# PCBBoardlayout.net
KiCad netlist of a schematic drawn in Altium Designer
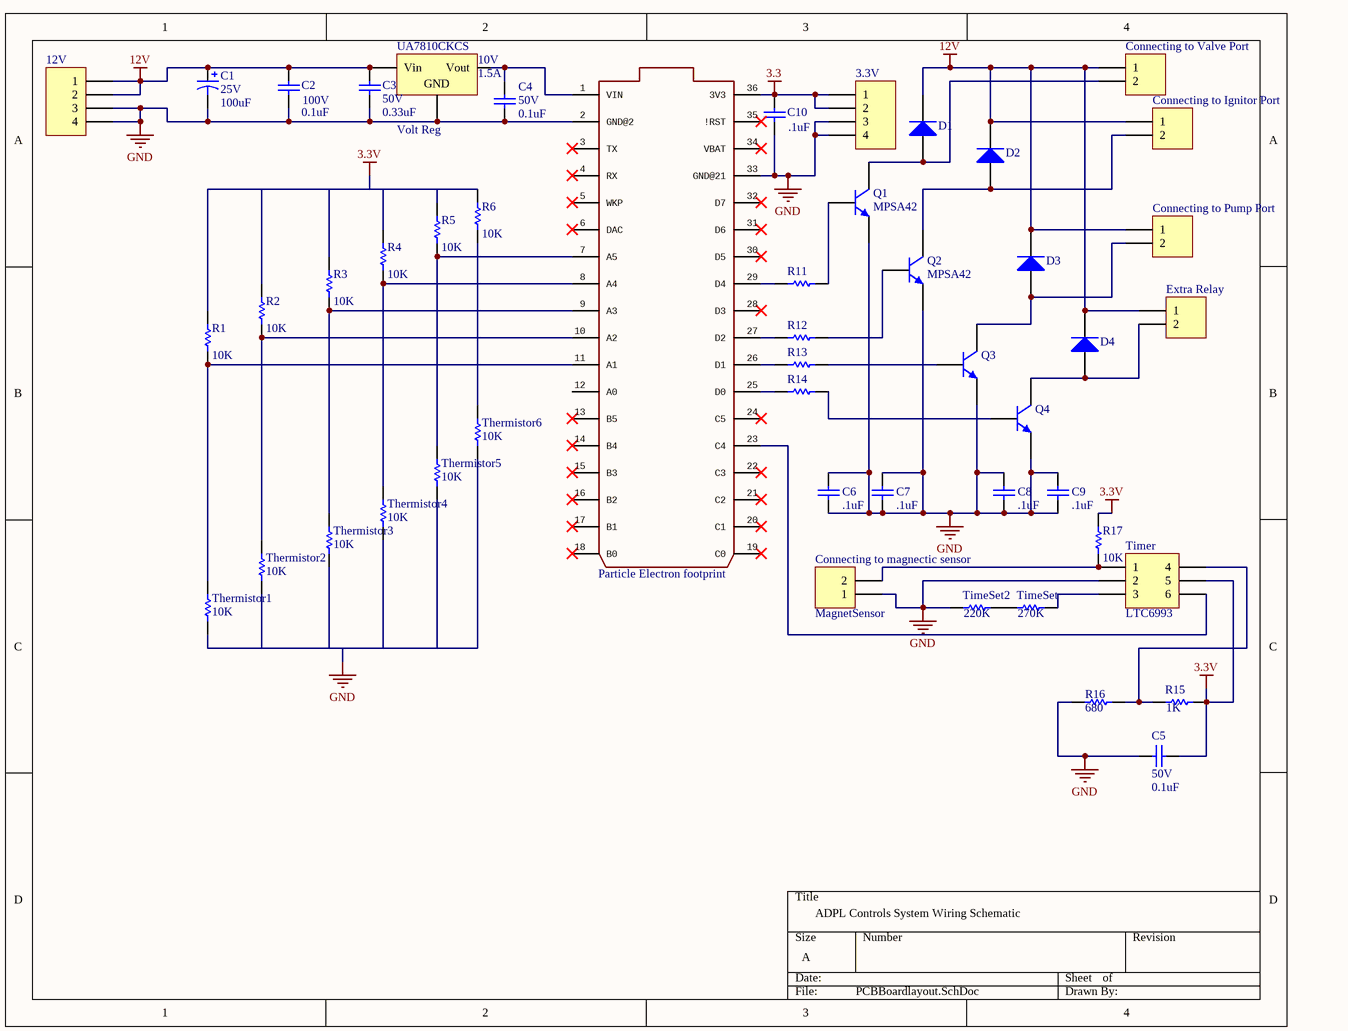
[diagram p0: PCBBoardlayout.SchDoc]

(export (version "E")
  (design (tool "Eeschema 10.0.6"))
  (components
    (comp (ref "3.3V")
      (value "~")
      (footprint "HDR1X4")
      (description "Header, 4-Pin")
      (fields (field (name "PUBLISHER") "Altium Limited"))
      (libsource (lib "Miscellaneous Connectors") (part "Header 4"))
    )
    (comp (ref "12V")
      (value "~")
      (footprint "HDR1X2")
      (description "Header, 4-Pin")
      (fields (field (name "PUBLISHER") "Altium Limited"))
      (libsource (lib "") (part "Header 4_1"))
    )
    (comp (ref "C1")
      (value "25V")
      (footprint "RB7.6-15")
      (description "Polarized Capacitor (Radial)")
      (fields (field (name "ALTIUM_VALUE") "100uF") (field (name "PUBLISHER") "Altium Limited"))
      (libsource (lib "Miscellaneous Devices") (part "Cap Pol1"))
    )
    (comp (ref "C2")
      (value "100V")
      (footprint "C1206")
      (description "Capacitor (Semiconductor SIM Model)")
      (fields
        (field (name "ALTIUM_VALUE") "0.1uF")
        (field (name "PART#") "581-SA111E104MAR")
        (field (name "PUBLISHER") "Altium Limited")
      )
      (libsource (lib "Miscellaneous Devices") (part "Cap Semi"))
    )
    (comp (ref "C3")
      (value "50V")
      (footprint "RAD-0.3")
      (description "Capacitor")
      (fields (field (name "ALTIUM_VALUE") "0.33uF") (field (name "PUBLISHER") "Altium Limited"))
      (libsource (lib "Miscellaneous Devices") (part "Cap"))
    )
    (comp (ref "C4")
      (value "50V")
      (footprint "RAD-0.3")
      (description "Capacitor")
      (fields (field (name "ALTIUM_VALUE") "0.1uF") (field (name "PUBLISHER") "Altium Limited"))
      (libsource (lib "Miscellaneous Devices") (part "Cap"))
    )
    (comp (ref "C5")
      (value "50V")
      (footprint "RAD-0.3")
      (description "Capacitor")
      (fields (field (name "ALTIUM_VALUE") "0.1uF") (field (name "PUBLISHER") "Altium Limited"))
      (libsource (lib "Miscellaneous Devices") (part "Cap"))
    )
    (comp (ref "C6")
      (value ".1uF")
      (footprint "C1206")
      (description "Capacitor (Semiconductor SIM Model)")
      (fields
        (field (name "PART#") "581-SA111E104MAR")
        (field (name "Comment") "BYCap")
        (field (name "PUBLISHER") "Altium Limited")
      )
      (libsource (lib "Miscellaneous Devices") (part "Cap Semi"))
    )
    (comp (ref "C7")
      (value ".1uF")
      (footprint "C1206")
      (description "Capacitor (Semiconductor SIM Model)")
      (fields
        (field (name "PART#") "581-SA111E104MAR")
        (field (name "Comment") "BYCap")
        (field (name "PUBLISHER") "Altium Limited")
      )
      (libsource (lib "Miscellaneous Devices") (part "Cap Semi"))
    )
    (comp (ref "C8")
      (value ".1uF")
      (footprint "C1206")
      (description "Capacitor (Semiconductor SIM Model)")
      (fields
        (field (name "PART#") "581-SA111E104MAR")
        (field (name "Comment") "BYCap")
        (field (name "PUBLISHER") "Altium Limited")
      )
      (libsource (lib "Miscellaneous Devices") (part "Cap Semi"))
    )
    (comp (ref "C9")
      (value ".1uF")
      (footprint "C1206")
      (description "Capacitor (Semiconductor SIM Model)")
      (fields
        (field (name "PART#") "581-SA111E104MAR")
        (field (name "Comment") "BYCap")
        (field (name "PUBLISHER") "Altium Limited")
      )
      (libsource (lib "Miscellaneous Devices") (part "Cap Semi"))
    )
    (comp (ref "C10")
      (value ".1uF")
      (footprint "C1206")
      (description "Capacitor (Semiconductor SIM Model)")
      (fields
        (field (name "PART#") "581-SA111E104MAR")
        (field (name "Comment") "BYCap")
        (field (name "PUBLISHER") "Altium Limited")
      )
      (libsource (lib "Miscellaneous Devices") (part "Cap Semi"))
    )
    (comp (ref "Connecting to Ignitor Port")
      (value "~")
      (footprint "HDR1X2")
      (description "Header, 2-Pin")
      (fields (field (name "PUBLISHER") "Altium Limited"))
      (libsource (lib "Miscellaneous Connectors") (part "Header 2"))
    )
    (comp (ref "Connecting to magnectic sensor")
      (value "MagnetSensor")
      (footprint "HDR1X2")
      (description "Header, 2-Pin")
      (fields
        (field (name "PUBLISHER") "Altium Limited")
        (field (name "SOURCE") "http://www.amazon.com/GERI-Counter-Digital-Proximity-Magnetic/dp/B01875612U/ref=sr_1_2?ie=UTF8&qid=1456764906&sr=8-2&keywords=magnetic+counter")
      )
      (libsource (lib "") (part "Header 2_1"))
    )
    (comp (ref "Connecting to Pump Port")
      (value "~")
      (footprint "HDR1X2")
      (description "Header, 2-Pin")
      (fields (field (name "PUBLISHER") "Altium Limited"))
      (libsource (lib "Miscellaneous Connectors") (part "Header 2"))
    )
    (comp (ref "Connecting to Valve Port")
      (value "~")
      (footprint "HDR1X2")
      (description "Header, 2-Pin")
      (fields (field (name "PUBLISHER") "Altium Limited"))
      (libsource (lib "Miscellaneous Connectors") (part "Header 2"))
    )
    (comp (ref "D1")
      (value "Diode 1N914")
      (footprint "DO-35")
      (description "High Conductance Fast Diode")
      (fields (field (name "PUBLISHER") "Altium Limited"))
      (libsource (lib "Miscellaneous Devices") (part "Diode 1N914"))
    )
    (comp (ref "D2")
      (value "Diode 1N914")
      (footprint "DO-35")
      (description "High Conductance Fast Diode")
      (fields (field (name "PUBLISHER") "Altium Limited"))
      (libsource (lib "Miscellaneous Devices") (part "Diode 1N914"))
    )
    (comp (ref "D3")
      (value "Diode 1N914")
      (footprint "DO-35")
      (description "High Conductance Fast Diode")
      (fields (field (name "PUBLISHER") "Altium Limited"))
      (libsource (lib "Miscellaneous Devices") (part "Diode 1N914"))
    )
    (comp (ref "D4")
      (value "Diode 1N914")
      (footprint "DO-35")
      (description "High Conductance Fast Diode")
      (fields (field (name "PUBLISHER") "Altium Limited"))
      (libsource (lib "Miscellaneous Devices") (part "Diode 1N914"))
    )
    (comp (ref "Extra Relay")
      (value "~")
      (footprint "HDR1X2")
      (description "Header, 2-Pin")
      (fields (field (name "PUBLISHER") "Altium Limited"))
      (libsource (lib "Miscellaneous Connectors") (part "Header 2"))
    )
    (comp (ref "Photon")
      (value "Particle Electron footprint")
      (footprint "ELECTRON")
      (libsource (lib "Particle-Devices") (part "ELECTRON_WITH_HEADERS"))
    )
    (comp (ref "Q1")
      (value "MPSA42")
      (footprint "Miscellaneous Devices:TO-92A")
      (description "NPN General Purpose Amplifier")
      (fields (field (name "PART#") "512-MPSA42") (field (name "PUBLISHER") "Altium Limited"))
      (libsource (lib "FSC Discrete BJT") (part "2N3904"))
    )
    (comp (ref "Q2")
      (value "MPSA42")
      (footprint "Miscellaneous Devices:TO-92A")
      (description "NPN General Purpose Amplifier")
      (fields (field (name "PART#") "512-MPSA42") (field (name "PUBLISHER") "Altium Limited"))
      (libsource (lib "FSC Discrete BJT") (part "2N3904"))
    )
    (comp (ref "Q3")
      (value "~")
      (footprint "Miscellaneous Devices:TO-92A")
      (description "NPN General Purpose Amplifier")
      (fields (field (name "PART#") "512-MPSA42") (field (name "PUBLISHER") "Altium Limited"))
      (libsource (lib "FSC Discrete BJT") (part "2N3904"))
    )
    (comp (ref "Q4")
      (value "MPSA42")
      (footprint "Miscellaneous Devices:TO-92A")
      (description "NPN General Purpose Amplifier")
      (fields (field (name "PART#") "512-MPSA42") (field (name "PUBLISHER") "Altium Limited"))
      (libsource (lib "FSC Discrete BJT") (part "2N3904"))
    )
    (comp (ref "R1")
      (value "10K")
      (footprint "AXIAL-0.3")
      (description "Resistor")
      (fields (field (name "Comment") "Res1") (field (name "PUBLISHER") "Altium Limited"))
      (libsource (lib "Miscellaneous Devices") (part "Res1"))
    )
    (comp (ref "R2")
      (value "10K")
      (footprint "AXIAL-0.3")
      (description "Resistor")
      (fields (field (name "Comment") "Res1") (field (name "PUBLISHER") "Altium Limited"))
      (libsource (lib "Miscellaneous Devices") (part "Res1"))
    )
    (comp (ref "R3")
      (value "10K")
      (footprint "AXIAL-0.3")
      (description "Resistor")
      (fields (field (name "Comment") "Res1") (field (name "PUBLISHER") "Altium Limited"))
      (libsource (lib "Miscellaneous Devices") (part "Res1"))
    )
    (comp (ref "R4")
      (value "10K")
      (footprint "AXIAL-0.3")
      (description "Resistor")
      (fields (field (name "Comment") "Res1") (field (name "PUBLISHER") "Altium Limited"))
      (libsource (lib "Miscellaneous Devices") (part "Res1"))
    )
    (comp (ref "R5")
      (value "10K")
      (footprint "AXIAL-0.3")
      (description "Resistor")
      (fields (field (name "Comment") "Res1") (field (name "PUBLISHER") "Altium Limited"))
      (libsource (lib "Miscellaneous Devices") (part "Res1"))
    )
    (comp (ref "R6")
      (value "10K")
      (footprint "AXIAL-0.3")
      (description "Resistor")
      (fields (field (name "Comment") "Res1") (field (name "PUBLISHER") "Altium Limited"))
      (libsource (lib "Miscellaneous Devices") (part "Res1"))
    )
    (comp (ref "R11")
      (value "Res1")
      (footprint "AXIAL-0.3")
      (description "Resistor")
      (fields (field (name "PUBLISHER") "Altium Limited"))
      (libsource (lib "Miscellaneous Devices") (part "Res1"))
    )
    (comp (ref "R12")
      (value "Res1")
      (footprint "AXIAL-0.3")
      (description "Resistor")
      (fields (field (name "PUBLISHER") "Altium Limited"))
      (libsource (lib "Miscellaneous Devices") (part "Res1"))
    )
    (comp (ref "R13")
      (value "Res1")
      (footprint "AXIAL-0.3")
      (description "Resistor")
      (fields (field (name "PUBLISHER") "Altium Limited"))
      (libsource (lib "Miscellaneous Devices") (part "Res1"))
    )
    (comp (ref "R14")
      (value "Res1")
      (footprint "AXIAL-0.3")
      (description "Resistor")
      (fields (field (name "PUBLISHER") "Altium Limited"))
      (libsource (lib "Miscellaneous Devices") (part "Res1"))
    )
    (comp (ref "R15")
      (value "1K")
      (footprint "AXIAL-0.3")
      (description "Resistor")
      (fields
        (field (name "PART#") "660-CF1/4C681J")
        (field (name "Comment") "Res14")
        (field (name "PUBLISHER") "Altium Limited")
      )
      (libsource (lib "Miscellaneous Devices") (part "Res1"))
    )
    (comp (ref "R16")
      (value "680")
      (footprint "AXIAL-0.3")
      (description "Resistor")
      (fields
        (field (name "PART#") "660-CF1/4CT52R102J")
        (field (name "Comment") "Res1")
        (field (name "PUBLISHER") "Altium Limited")
      )
      (libsource (lib "Miscellaneous Devices") (part "Res1"))
    )
    (comp (ref "R17")
      (value "10K")
      (footprint "AXIAL-0.3")
      (description "Resistor")
      (fields (field (name "Comment") "Res1") (field (name "PUBLISHER") "Altium Limited"))
      (libsource (lib "Miscellaneous Devices") (part "Res1"))
    )
    (comp (ref "Thermistor1")
      (value "10K")
      (footprint "AXIAL-0.3")
      (description "Resistor")
      (fields
        (field (name "PART#") "NTCAIMME3C90373")
        (field (name "Comment") "Res1")
        (field (name "PUBLISHER") "Altium Limited")
      )
      (libsource (lib "Miscellaneous Devices") (part "Res1"))
    )
    (comp (ref "Thermistor2")
      (value "10K")
      (footprint "AXIAL-0.3")
      (description "Resistor")
      (fields
        (field (name "PART#") "NTCAIMME3C90373")
        (field (name "Comment") "Res1")
        (field (name "PUBLISHER") "Altium Limited")
      )
      (libsource (lib "Miscellaneous Devices") (part "Res1"))
    )
    (comp (ref "Thermistor3")
      (value "10K")
      (footprint "AXIAL-0.3")
      (description "Resistor")
      (fields
        (field (name "PART#") "Dwyer I2-1B062")
        (field (name "Comment") "Res1")
        (field (name "PUBLISHER") "Altium Limited")
      )
      (libsource (lib "Miscellaneous Devices") (part "Res1"))
    )
    (comp (ref "Thermistor4")
      (value "10K")
      (footprint "AXIAL-0.3")
      (description "Resistor")
      (fields
        (field (name "PART#") "NTCAIMME3C90373")
        (field (name "Comment") "Res1")
        (field (name "PUBLISHER") "Altium Limited")
      )
      (libsource (lib "Miscellaneous Devices") (part "Res1"))
    )
    (comp (ref "Thermistor5")
      (value "10K")
      (footprint "AXIAL-0.3")
      (description "Resistor")
      (fields
        (field (name "PART#") "NTCAIMME3C90373")
        (field (name "Comment") "Res1")
        (field (name "PUBLISHER") "Altium Limited")
      )
      (libsource (lib "Miscellaneous Devices") (part "Res1"))
    )
    (comp (ref "Thermistor6")
      (value "10K")
      (footprint "AXIAL-0.3")
      (description "Resistor")
      (fields
        (field (name "PART#") "NTCAIMME3C90373")
        (field (name "Comment") "Res1")
        (field (name "PUBLISHER") "Altium Limited")
      )
      (libsource (lib "Miscellaneous Devices") (part "Res1"))
    )
    (comp (ref "Timer")
      (value "LTC6993")
      (footprint "PCB_Footprints:LTC6993")
      (libsource (lib "custom_components") (part "LTC6993"))
    )
    (comp (ref "TimeSet")
      (value "270K")
      (footprint "AXIAL-0.3")
      (description "Resistor")
      (fields
        (field (name "PART#") "660-CF1/4CT52R274J")
        (field (name "Comment") "Res1")
        (field (name "PUBLISHER") "Altium Limited")
      )
      (libsource (lib "Miscellaneous Devices") (part "Res1"))
    )
    (comp (ref "TimeSet2")
      (value "220K")
      (footprint "AXIAL-0.3")
      (description "Resistor")
      (fields
        (field (name "PART#") "660-CF1/4CT52R224J")
        (field (name "Comment") "Res1")
        (field (name "PUBLISHER") "Altium Limited")
      )
      (libsource (lib "Miscellaneous Devices") (part "Res1"))
    )
    (comp (ref "UA7810CKCS")
      (value "Volt Reg")
      (footprint "D2PAK_N")
      (description "Voltage Regulator")
      (fields
        (field (name "PART#") "UA7810CKCS")
        (field (name "VOLTAGE OUTPUT") "10V")
        (field (name "CURRENT OUTPUT") "1.5A")
        (field (name "PUBLISHER") "Altium Limited")
      )
      (libsource (lib "Miscellaneous Devices") (part "Volt Reg"))
    )
  )
  (nets
    (net (code "1") (name "3.3") (class "Default")
      (node (ref "3.3V") (pin "1") (pinfunction "1_1") (pintype "passive"))
      (node (ref "3.3V") (pin "2") (pinfunction "2_2") (pintype "passive"))
      (node (ref "C10") (pin "2") (pinfunction "2_2") (pintype "passive"))
      (node (ref "Photon") (pin "36") (pinfunction "3V3_36") (pintype "power_in"))
    )
    (net (code "2") (name "3.3V") (class "Default")
      (node (ref "C5") (pin "1") (pinfunction "1_1") (pintype "passive"))
      (node (ref "R15") (pin "1") (pinfunction "1_1") (pintype "passive"))
      (node (ref "R17") (pin "2") (pinfunction "2_2") (pintype "passive"))
      (node (ref "Timer") (pin "5") (pinfunction "5_5") (pintype "passive"))
    )
    (net (code "3") (name "12V") (class "Default")
      (node (ref "12V") (pin "1") (pinfunction "1_1") (pintype "passive"))
      (node (ref "12V") (pin "2") (pinfunction "2_2") (pintype "passive"))
      (node (ref "C1") (pin "1") (pinfunction "1_1") (pintype "passive"))
      (node (ref "C2") (pin "2") (pinfunction "2_2") (pintype "passive"))
      (node (ref "C3") (pin "2") (pinfunction "2_2") (pintype "passive"))
      (node (ref "Connecting to Ignitor Port") (pin "1") (pinfunction "1_1") (pintype "passive"))
      (node (ref "Connecting to Pump Port") (pin "1") (pinfunction "1_1") (pintype "passive"))
      (node (ref "Connecting to Valve Port") (pin "1") (pinfunction "1_1") (pintype "passive"))
      (node (ref "D1") (pin "2") (pinfunction "K_2") (pintype "passive"))
      (node (ref "D2") (pin "2") (pinfunction "K_2") (pintype "passive"))
      (node (ref "D3") (pin "2") (pinfunction "K_2") (pintype "passive"))
      (node (ref "D4") (pin "2") (pinfunction "K_2") (pintype "passive"))
      (node (ref "Extra Relay") (pin "1") (pinfunction "1_1") (pintype "passive"))
      (node (ref "UA7810CKCS") (pin "1") (pinfunction "Vin_1") (pintype "passive"))
    )
    (net (code "4") (name "GND") (class "Default")
      (node (ref "12V") (pin "3") (pinfunction "3_3") (pintype "passive"))
      (node (ref "12V") (pin "4") (pinfunction "4_4") (pintype "passive"))
      (node (ref "3.3V") (pin "3") (pinfunction "3_3") (pintype "passive"))
      (node (ref "3.3V") (pin "4") (pinfunction "4_4") (pintype "passive"))
      (node (ref "C1") (pin "2") (pinfunction "2_2") (pintype "passive"))
      (node (ref "C10") (pin "1") (pinfunction "1_1") (pintype "passive"))
      (node (ref "C2") (pin "1") (pinfunction "1_1") (pintype "passive"))
      (node (ref "C3") (pin "1") (pinfunction "1_1") (pintype "passive"))
      (node (ref "C4") (pin "1") (pinfunction "1_1") (pintype "passive"))
      (node (ref "C5") (pin "2") (pinfunction "2_2") (pintype "passive"))
      (node (ref "C6") (pin "1") (pinfunction "1_1") (pintype "passive"))
      (node (ref "C6") (pin "2") (pinfunction "2_2") (pintype "passive"))
      (node (ref "C7") (pin "1") (pinfunction "1_1") (pintype "passive"))
      (node (ref "C7") (pin "2") (pinfunction "2_2") (pintype "passive"))
      (node (ref "C8") (pin "1") (pinfunction "1_1") (pintype "passive"))
      (node (ref "C8") (pin "2") (pinfunction "2_2") (pintype "passive"))
      (node (ref "C9") (pin "1") (pinfunction "1_1") (pintype "passive"))
      (node (ref "C9") (pin "2") (pinfunction "2_2") (pintype "passive"))
      (node (ref "Connecting to magnectic sensor") (pin "1") (pinfunction "1_1") (pintype "passive"))
      (node (ref "Photon") (pin "2") (pinfunction "GND@2_2") (pintype "power_in"))
      (node (ref "Photon") (pin "33") (pinfunction "GND@21_33") (pintype "power_in"))
      (node (ref "Q1") (pin "1") (pinfunction "E_1") (pintype "passive"))
      (node (ref "Q2") (pin "1") (pinfunction "E_1") (pintype "passive"))
      (node (ref "Q3") (pin "1") (pinfunction "E_1") (pintype "passive"))
      (node (ref "Q4") (pin "1") (pinfunction "E_1") (pintype "passive"))
      (node (ref "R16") (pin "2") (pinfunction "2_2") (pintype "passive"))
      (node (ref "TimeSet2") (pin "1") (pinfunction "1_1") (pintype "passive"))
      (node (ref "Timer") (pin "2") (pinfunction "2_2") (pintype "passive"))
      (node (ref "UA7810CKCS") (pin "2") (pinfunction "GND_2") (pintype "passive"))
    )
    (net (code "5") (name "Net-(Connecting to magnectic sensor-Pad2)") (class "Default")
      (node (ref "Connecting to magnectic sensor") (pin "2") (pinfunction "2_2") (pintype "passive"))
      (node (ref "R17") (pin "1") (pinfunction "1_1") (pintype "passive"))
      (node (ref "Timer") (pin "1") (pinfunction "1_1") (pintype "passive"))
    )
    (net (code "6") (name "Net-(D1-A)") (class "Default")
      (node (ref "Connecting to Valve Port") (pin "2") (pinfunction "2_2") (pintype "passive"))
      (node (ref "D1") (pin "1") (pinfunction "A_1") (pintype "passive"))
      (node (ref "Q1") (pin "3") (pinfunction "C_3") (pintype "passive"))
    )
    (net (code "7") (name "Net-(D2-A)") (class "Default")
      (node (ref "Connecting to Ignitor Port") (pin "2") (pinfunction "2_2") (pintype "passive"))
      (node (ref "D2") (pin "1") (pinfunction "A_1") (pintype "passive"))
      (node (ref "Q2") (pin "3") (pinfunction "C_3") (pintype "passive"))
    )
    (net (code "8") (name "Net-(D3-A)") (class "Default")
      (node (ref "Connecting to Pump Port") (pin "2") (pinfunction "2_2") (pintype "passive"))
      (node (ref "D3") (pin "1") (pinfunction "A_1") (pintype "passive"))
      (node (ref "Q3") (pin "3") (pinfunction "C_3") (pintype "passive"))
    )
    (net (code "9") (name "Net-(D4-A)") (class "Default")
      (node (ref "D4") (pin "1") (pinfunction "A_1") (pintype "passive"))
      (node (ref "Extra Relay") (pin "2") (pinfunction "2_2") (pintype "passive"))
      (node (ref "Q4") (pin "3") (pinfunction "C_3") (pintype "passive"))
    )
    (net (code "10") (name "Net-(Photon-A1)") (class "Default")
      (node (ref "Photon") (pin "11") (pinfunction "A1_11") (pintype "passive"))
      (node (ref "R1") (pin "1") (pinfunction "1_1") (pintype "passive"))
      (node (ref "Thermistor1") (pin "2") (pinfunction "2_2") (pintype "passive"))
    )
    (net (code "11") (name "Net-(Photon-A2)") (class "Default")
      (node (ref "Photon") (pin "10") (pinfunction "A2_10") (pintype "passive"))
      (node (ref "R2") (pin "1") (pinfunction "1_1") (pintype "passive"))
      (node (ref "Thermistor2") (pin "2") (pinfunction "2_2") (pintype "passive"))
    )
    (net (code "12") (name "Net-(Photon-A3)") (class "Default")
      (node (ref "Photon") (pin "9") (pinfunction "A3_9") (pintype "passive"))
      (node (ref "R3") (pin "1") (pinfunction "1_1") (pintype "passive"))
      (node (ref "Thermistor3") (pin "2") (pinfunction "2_2") (pintype "passive"))
    )
    (net (code "13") (name "Net-(Photon-A4)") (class "Default")
      (node (ref "Photon") (pin "8") (pinfunction "A4_8") (pintype "passive"))
      (node (ref "R4") (pin "1") (pinfunction "1_1") (pintype "passive"))
      (node (ref "Thermistor4") (pin "2") (pinfunction "2_2") (pintype "passive"))
    )
    (net (code "14") (name "Net-(Photon-A5)") (class "Default")
      (node (ref "Photon") (pin "7") (pinfunction "A5_7") (pintype "passive"))
      (node (ref "R5") (pin "1") (pinfunction "1_1") (pintype "passive"))
      (node (ref "Thermistor5") (pin "2") (pinfunction "2_2") (pintype "passive"))
    )
    (net (code "15") (name "Net-(Photon-C4)") (class "Default")
      (node (ref "Photon") (pin "23") (pinfunction "C4_23") (pintype "passive"))
      (node (ref "Timer") (pin "6") (pinfunction "6_6") (pintype "passive"))
    )
    (net (code "16") (name "Net-(Photon-D0)") (class "Default")
      (node (ref "Photon") (pin "25") (pinfunction "D0_25") (pintype "passive"))
      (node (ref "R14") (pin "1") (pinfunction "1_1") (pintype "passive"))
    )
    (net (code "17") (name "Net-(Photon-D1)") (class "Default")
      (node (ref "Photon") (pin "26") (pinfunction "D1_26") (pintype "passive"))
      (node (ref "R13") (pin "1") (pinfunction "1_1") (pintype "passive"))
    )
    (net (code "18") (name "Net-(Photon-D2)") (class "Default")
      (node (ref "Photon") (pin "27") (pinfunction "D2_27") (pintype "passive"))
      (node (ref "R12") (pin "1") (pinfunction "1_1") (pintype "passive"))
    )
    (net (code "19") (name "Net-(Photon-D4)") (class "Default")
      (node (ref "Photon") (pin "29") (pinfunction "D4_29") (pintype "passive"))
      (node (ref "R11") (pin "1") (pinfunction "1_1") (pintype "passive"))
    )
    (net (code "20") (name "Net-(Photon-VIN)") (class "Default")
      (node (ref "C4") (pin "2") (pinfunction "2_2") (pintype "passive"))
      (node (ref "Photon") (pin "1") (pinfunction "VIN_1") (pintype "power_in"))
      (node (ref "UA7810CKCS") (pin "3") (pinfunction "Vout_3") (pintype "passive"))
    )
    (net (code "21") (name "Net-(Q1-B)") (class "Default")
      (node (ref "Q1") (pin "2") (pinfunction "B_2") (pintype "passive"))
      (node (ref "R11") (pin "2") (pinfunction "2_2") (pintype "passive"))
    )
    (net (code "22") (name "Net-(Q2-B)") (class "Default")
      (node (ref "Q2") (pin "2") (pinfunction "B_2") (pintype "passive"))
      (node (ref "R12") (pin "2") (pinfunction "2_2") (pintype "passive"))
    )
    (net (code "23") (name "Net-(Q3-B)") (class "Default")
      (node (ref "Q3") (pin "2") (pinfunction "B_2") (pintype "passive"))
      (node (ref "R13") (pin "2") (pinfunction "2_2") (pintype "passive"))
    )
    (net (code "24") (name "Net-(Q4-B)") (class "Default")
      (node (ref "Q4") (pin "2") (pinfunction "B_2") (pintype "passive"))
      (node (ref "R14") (pin "2") (pinfunction "2_2") (pintype "passive"))
    )
    (net (code "25") (name "Net-(R6-Pad1)") (class "Default")
      (node (ref "R6") (pin "1") (pinfunction "1_1") (pintype "passive"))
      (node (ref "Thermistor6") (pin "2") (pinfunction "2_2") (pintype "passive"))
    )
    (net (code "26") (name "Net-(R15-Pad2)") (class "Default")
      (node (ref "R15") (pin "2") (pinfunction "2_2") (pintype "passive"))
      (node (ref "R16") (pin "1") (pinfunction "1_1") (pintype "passive"))
      (node (ref "Timer") (pin "4") (pinfunction "4_4") (pintype "passive"))
    )
    (net (code "27") (name "Net-(TimeSet-Pad1)") (class "Default")
      (node (ref "TimeSet") (pin "1") (pinfunction "1_1") (pintype "passive"))
      (node (ref "TimeSet2") (pin "2") (pinfunction "2_2") (pintype "passive"))
    )
    (net (code "28") (name "Net-(TimeSet-Pad2)") (class "Default")
      (node (ref "TimeSet") (pin "2") (pinfunction "2_2") (pintype "passive"))
      (node (ref "Timer") (pin "3") (pinfunction "3_3") (pintype "passive"))
    )
    (net (code "29") (name "unconnected-(Photon-!RST-Pad35)") (class "Default")
      (node (ref "Photon") (pin "35") (pinfunction "!RST_35") (pintype "passive+no_connect"))
    )
    (net (code "30") (name "unconnected-(Photon-A0-Pad12)") (class "Default")
      (node (ref "Photon") (pin "12") (pinfunction "A0_12") (pintype "passive"))
    )
    (net (code "31") (name "unconnected-(Photon-B0-Pad18)") (class "Default")
      (node (ref "Photon") (pin "18") (pinfunction "B0_18") (pintype "passive+no_connect"))
    )
    (net (code "32") (name "unconnected-(Photon-B1-Pad17)") (class "Default")
      (node (ref "Photon") (pin "17") (pinfunction "B1_17") (pintype "passive+no_connect"))
    )
    (net (code "33") (name "unconnected-(Photon-B2-Pad16)") (class "Default")
      (node (ref "Photon") (pin "16") (pinfunction "B2_16") (pintype "passive+no_connect"))
    )
    (net (code "34") (name "unconnected-(Photon-B3-Pad15)") (class "Default")
      (node (ref "Photon") (pin "15") (pinfunction "B3_15") (pintype "passive+no_connect"))
    )
    (net (code "35") (name "unconnected-(Photon-B4-Pad14)") (class "Default")
      (node (ref "Photon") (pin "14") (pinfunction "B4_14") (pintype "passive+no_connect"))
    )
    (net (code "36") (name "unconnected-(Photon-B5-Pad13)") (class "Default")
      (node (ref "Photon") (pin "13") (pinfunction "B5_13") (pintype "passive+no_connect"))
    )
    (net (code "37") (name "unconnected-(Photon-C0-Pad19)") (class "Default")
      (node (ref "Photon") (pin "19") (pinfunction "C0_19") (pintype "passive+no_connect"))
    )
    (net (code "38") (name "unconnected-(Photon-C1-Pad20)") (class "Default")
      (node (ref "Photon") (pin "20") (pinfunction "C1_20") (pintype "passive+no_connect"))
    )
    (net (code "39") (name "unconnected-(Photon-C2-Pad21)") (class "Default")
      (node (ref "Photon") (pin "21") (pinfunction "C2_21") (pintype "passive+no_connect"))
    )
    (net (code "40") (name "unconnected-(Photon-C3-Pad22)") (class "Default")
      (node (ref "Photon") (pin "22") (pinfunction "C3_22") (pintype "passive+no_connect"))
    )
    (net (code "41") (name "unconnected-(Photon-C5-Pad24)") (class "Default")
      (node (ref "Photon") (pin "24") (pinfunction "C5_24") (pintype "passive+no_connect"))
    )
    (net (code "42") (name "unconnected-(Photon-D3-Pad28)") (class "Default")
      (node (ref "Photon") (pin "28") (pinfunction "D3_28") (pintype "passive+no_connect"))
    )
    (net (code "43") (name "unconnected-(Photon-D5-Pad30)") (class "Default")
      (node (ref "Photon") (pin "30") (pinfunction "D5_30") (pintype "passive+no_connect"))
    )
    (net (code "44") (name "unconnected-(Photon-D6-Pad31)") (class "Default")
      (node (ref "Photon") (pin "31") (pinfunction "D6_31") (pintype "passive+no_connect"))
    )
    (net (code "45") (name "unconnected-(Photon-D7-Pad32)") (class "Default")
      (node (ref "Photon") (pin "32") (pinfunction "D7_32") (pintype "passive+no_connect"))
    )
    (net (code "46") (name "unconnected-(Photon-DAC-Pad6)") (class "Default")
      (node (ref "Photon") (pin "6") (pinfunction "DAC_6") (pintype "passive+no_connect"))
    )
    (net (code "47") (name "unconnected-(Photon-RX-Pad4)") (class "Default")
      (node (ref "Photon") (pin "4") (pinfunction "RX_4") (pintype "passive+no_connect"))
    )
    (net (code "48") (name "unconnected-(Photon-TX-Pad3)") (class "Default")
      (node (ref "Photon") (pin "3") (pinfunction "TX_3") (pintype "passive+no_connect"))
    )
    (net (code "49") (name "unconnected-(Photon-VBAT-Pad34)") (class "Default")
      (node (ref "Photon") (pin "34") (pinfunction "VBAT_34") (pintype "power_in+no_connect"))
    )
    (net (code "50") (name "unconnected-(Photon-WKP-Pad5)") (class "Default")
      (node (ref "Photon") (pin "5") (pinfunction "WKP_5") (pintype "passive+no_connect"))
    )
    (net (code "51") (name "unconnected-(R1-Pad2)") (class "Default")
      (node (ref "R1") (pin "2") (pinfunction "2_2") (pintype "passive"))
    )
    (net (code "52") (name "unconnected-(R2-Pad2)") (class "Default")
      (node (ref "R2") (pin "2") (pinfunction "2_2") (pintype "passive"))
    )
    (net (code "53") (name "unconnected-(R3-Pad2)") (class "Default")
      (node (ref "R3") (pin "2") (pinfunction "2_2") (pintype "passive"))
    )
    (net (code "54") (name "unconnected-(R4-Pad2)") (class "Default")
      (node (ref "R4") (pin "2") (pinfunction "2_2") (pintype "passive"))
    )
    (net (code "55") (name "unconnected-(R5-Pad2)") (class "Default")
      (node (ref "R5") (pin "2") (pinfunction "2_2") (pintype "passive"))
    )
    (net (code "56") (name "unconnected-(R6-Pad2)") (class "Default")
      (node (ref "R6") (pin "2") (pinfunction "2_2") (pintype "passive"))
    )
    (net (code "57") (name "unconnected-(Thermistor1-Pad1)") (class "Default")
      (node (ref "Thermistor1") (pin "1") (pinfunction "1_1") (pintype "passive"))
    )
    (net (code "58") (name "unconnected-(Thermistor2-Pad1)") (class "Default")
      (node (ref "Thermistor2") (pin "1") (pinfunction "1_1") (pintype "passive"))
    )
    (net (code "59") (name "unconnected-(Thermistor3-Pad1)") (class "Default")
      (node (ref "Thermistor3") (pin "1") (pinfunction "1_1") (pintype "passive"))
    )
    (net (code "60") (name "unconnected-(Thermistor4-Pad1)") (class "Default")
      (node (ref "Thermistor4") (pin "1") (pinfunction "1_1") (pintype "passive"))
    )
    (net (code "61") (name "unconnected-(Thermistor5-Pad1)") (class "Default")
      (node (ref "Thermistor5") (pin "1") (pinfunction "1_1") (pintype "passive"))
    )
    (net (code "62") (name "unconnected-(Thermistor6-Pad1)") (class "Default")
      (node (ref "Thermistor6") (pin "1") (pinfunction "1_1") (pintype "passive"))
    )
  )
)
